# IMU_LSM9DS1_SCH.net
KiCad netlist of a schematic drawn in Altium Designer
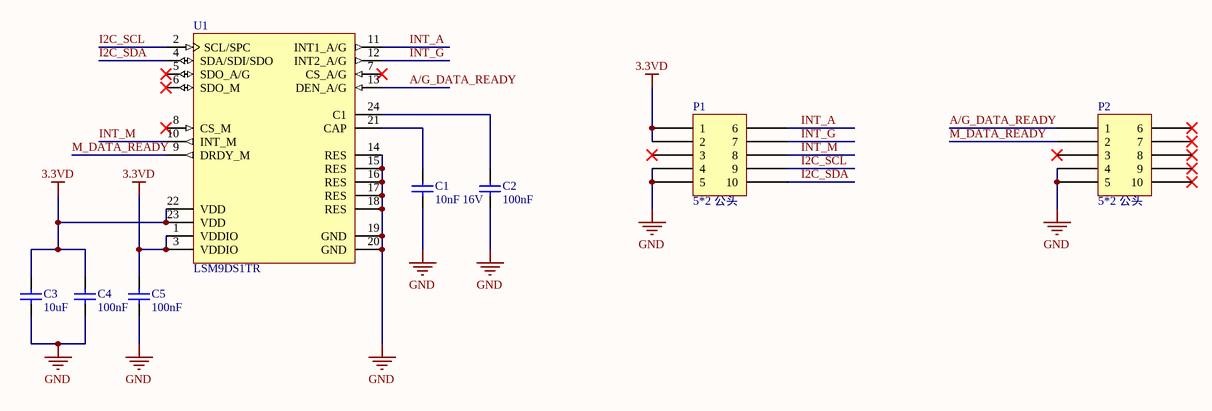
[diagram p0: IMU_LSM9DS1_SCH.SchDoc]

(export (version "E")
  (design (tool "Eeschema 10.0.6"))
  (components
    (comp (ref "C1")
      (value "10nF 16V")
      (footprint "CAPC0603(1608)100_N")
      (description "CAP 10nF 16V ±10% 0603")
      (fields (field (name "TOLERANCE") "Â±10%") (field (name "MANUFACTURER") "Vishay Vitramon"))
      (libsource (lib "NanoEEG_v2_MCU") (part "CMP-1035-02588-1"))
    )
    (comp (ref "C2")
      (value "100nF")
      (footprint "CAPC0603(1608)100_N")
      (description "CAP 10nF 16V ±10% 0603")
      (fields (field (name "TOLERANCE") "Â±10%") (field (name "MANUFACTURER") "Vishay Vitramon"))
      (libsource (lib "NanoEEG_v2_MCU") (part "CMP-1035-02588-1"))
    )
    (comp (ref "C3")
      (value "10uF")
      (footprint "CAPC0603(1608)100_N")
      (description "CAP 10nF 16V ±10% 0603")
      (fields (field (name "TOLERANCE") "Â±10%") (field (name "MANUFACTURER") "Vishay Vitramon"))
      (libsource (lib "NanoEEG_v2_MCU") (part "CMP-1035-02588-1"))
    )
    (comp (ref "C4")
      (value "100nF")
      (footprint "CAPC0603(1608)100_N")
      (description "CAP 10nF 16V ±10% 0603")
      (fields (field (name "TOLERANCE") "Â±10%") (field (name "MANUFACTURER") "Vishay Vitramon"))
      (libsource (lib "NanoEEG_v2_MCU") (part "CMP-1035-02588-1"))
    )
    (comp (ref "C5")
      (value "100nF")
      (footprint "CAPC0603(1608)100_N")
      (description "CAP 10nF 16V ±10% 0603")
      (fields (field (name "TOLERANCE") "Â±10%") (field (name "MANUFACTURER") "Vishay Vitramon"))
      (libsource (lib "NanoEEG_v2_MCU") (part "CMP-1035-02588-1"))
    )
    (comp (ref "P1") (value "5*2 公头") (footprint "10pin 公头") (libsource (lib "Schlib1") (part "5*2 公头")))
    (comp (ref "P2") (value "5*2 公头") (footprint "10pin 公头") (libsource (lib "Schlib1") (part "5*2 公头")))
    (comp (ref "U1")
      (value "LSM9DS1TR")
      (footprint "STM-LGA-24_3500X3000X1000")
      (fields (field (name "PARTNUMBER") "LSM9DS1") (field (name "MANUFACTURER") "STMicroelectronics"))
      (libsource (lib "Altium Content Vault") (part "STM-LSM9DS1-24"))
    )
  )
  (nets
    (net (code "1") (name "/A{slash}G_DATA_READY") (class "Default")
      (node (ref "P2") (pin "1") (pinfunction "1_1") (pintype "passive"))
      (node (ref "U1") (pin "13") (pinfunction "DEN_A/G_13") (pintype "input"))
    )
    (net (code "2") (name "/I2C_SCL") (class "Default")
      (node (ref "P1") (pin "9") (pinfunction "9_9") (pintype "passive"))
      (node (ref "U1") (pin "2") (pinfunction "SCL/SPC_2") (pintype "input"))
    )
    (net (code "3") (name "/I2C_SDA") (class "Default")
      (node (ref "P1") (pin "10") (pinfunction "10_10") (pintype "passive"))
      (node (ref "U1") (pin "4") (pinfunction "SDA/SDI/SDO_4") (pintype "bidirectional"))
    )
    (net (code "4") (name "/INT_A") (class "Default")
      (node (ref "P1") (pin "6") (pinfunction "6_6") (pintype "passive"))
      (node (ref "U1") (pin "11") (pinfunction "INT1_A/G_11") (pintype "output"))
    )
    (net (code "5") (name "/INT_G") (class "Default")
      (node (ref "P1") (pin "7") (pinfunction "7_7") (pintype "passive"))
      (node (ref "U1") (pin "12") (pinfunction "INT2_A/G_12") (pintype "output"))
    )
    (net (code "6") (name "/INT_M") (class "Default")
      (node (ref "P1") (pin "8") (pinfunction "8_8") (pintype "passive"))
      (node (ref "U1") (pin "10") (pinfunction "INT_M_10") (pintype "output"))
    )
    (net (code "7") (name "/M_DATA_READY") (class "Default")
      (node (ref "P2") (pin "2") (pinfunction "2_2") (pintype "passive"))
      (node (ref "U1") (pin "9") (pinfunction "DRDY_M_9") (pintype "output"))
    )
    (net (code "8") (name "3.3VD") (class "Default")
      (node (ref "C3") (pin "2") (pinfunction "2_2") (pintype "passive"))
      (node (ref "C4") (pin "2") (pinfunction "2_2") (pintype "passive"))
      (node (ref "C5") (pin "2") (pinfunction "2_2") (pintype "passive"))
      (node (ref "P1") (pin "1") (pinfunction "1_1") (pintype "passive"))
      (node (ref "P1") (pin "2") (pinfunction "2_2") (pintype "passive"))
      (node (ref "U1") (pin "1") (pinfunction "VDDIO_1") (pintype "power_in"))
      (node (ref "U1") (pin "22") (pinfunction "VDD_22") (pintype "power_in"))
      (node (ref "U1") (pin "23") (pinfunction "VDD_23") (pintype "power_in"))
      (node (ref "U1") (pin "3") (pinfunction "VDDIO_3") (pintype "power_in"))
    )
    (net (code "9") (name "GND") (class "Default")
      (node (ref "C1") (pin "1") (pinfunction "1_1") (pintype "passive"))
      (node (ref "C2") (pin "1") (pinfunction "1_1") (pintype "passive"))
      (node (ref "C3") (pin "1") (pinfunction "1_1") (pintype "passive"))
      (node (ref "C4") (pin "1") (pinfunction "1_1") (pintype "passive"))
      (node (ref "C5") (pin "1") (pinfunction "1_1") (pintype "passive"))
      (node (ref "P1") (pin "4") (pinfunction "4_4") (pintype "passive"))
      (node (ref "P1") (pin "5") (pinfunction "5_5") (pintype "passive"))
      (node (ref "P2") (pin "4") (pinfunction "4_4") (pintype "passive"))
      (node (ref "P2") (pin "5") (pinfunction "5_5") (pintype "passive"))
      (node (ref "U1") (pin "14") (pinfunction "RES_14") (pintype "passive"))
      (node (ref "U1") (pin "15") (pinfunction "RES_15") (pintype "passive"))
      (node (ref "U1") (pin "16") (pinfunction "RES_16") (pintype "passive"))
      (node (ref "U1") (pin "17") (pinfunction "RES_17") (pintype "passive"))
      (node (ref "U1") (pin "18") (pinfunction "RES_18") (pintype "passive"))
      (node (ref "U1") (pin "19") (pinfunction "GND_19") (pintype "power_in"))
      (node (ref "U1") (pin "20") (pinfunction "GND_20") (pintype "power_in"))
    )
    (net (code "10") (name "Net-(U1-C1)") (class "Default")
      (node (ref "C2") (pin "2") (pinfunction "2_2") (pintype "passive"))
      (node (ref "U1") (pin "24") (pinfunction "C1_24") (pintype "passive"))
    )
    (net (code "11") (name "Net-(U1-CAP)") (class "Default")
      (node (ref "C1") (pin "2") (pinfunction "2_2") (pintype "passive"))
      (node (ref "U1") (pin "21") (pinfunction "CAP_21") (pintype "passive"))
    )
    (net (code "12") (name "unconnected-(P1-Pad3)") (class "Default")
      (node (ref "P1") (pin "3") (pinfunction "3_3") (pintype "passive+no_connect"))
    )
    (net (code "13") (name "unconnected-(P2-Pad3)") (class "Default")
      (node (ref "P2") (pin "3") (pinfunction "3_3") (pintype "passive+no_connect"))
    )
    (net (code "14") (name "unconnected-(P2-Pad6)") (class "Default")
      (node (ref "P2") (pin "6") (pinfunction "6_6") (pintype "passive+no_connect"))
    )
    (net (code "15") (name "unconnected-(P2-Pad7)") (class "Default")
      (node (ref "P2") (pin "7") (pinfunction "7_7") (pintype "passive+no_connect"))
    )
    (net (code "16") (name "unconnected-(P2-Pad8)") (class "Default")
      (node (ref "P2") (pin "8") (pinfunction "8_8") (pintype "passive+no_connect"))
    )
    (net (code "17") (name "unconnected-(P2-Pad9)") (class "Default")
      (node (ref "P2") (pin "9") (pinfunction "9_9") (pintype "passive+no_connect"))
    )
    (net (code "18") (name "unconnected-(P2-Pad10)") (class "Default")
      (node (ref "P2") (pin "10") (pinfunction "10_10") (pintype "passive+no_connect"))
    )
    (net (code "19") (name "unconnected-(U1-CS_A{slash}G-Pad7)") (class "Default")
      (node (ref "U1") (pin "7") (pinfunction "CS_A/G_7") (pintype "input+no_connect"))
    )
    (net (code "20") (name "unconnected-(U1-CS_M-Pad8)") (class "Default")
      (node (ref "U1") (pin "8") (pinfunction "CS_M_8") (pintype "input+no_connect"))
    )
    (net (code "21") (name "unconnected-(U1-SDO_A{slash}G-Pad5)") (class "Default")
      (node (ref "U1") (pin "5") (pinfunction "SDO_A/G_5") (pintype "bidirectional+no_connect"))
    )
    (net (code "22") (name "unconnected-(U1-SDO_M-Pad6)") (class "Default")
      (node (ref "U1") (pin "6") (pinfunction "SDO_M_6") (pintype "bidirectional+no_connect"))
    )
  )
)
